# Sheet2.net
KiCad netlist of a schematic drawn in Altium Designer
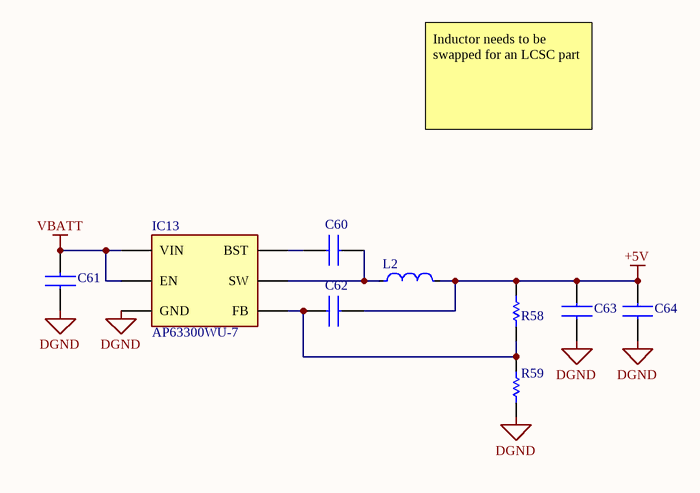
[diagram p0: Sheet2.SchDoc]

(export (version "E")
  (design (tool "Eeschema 10.0.6"))
  (components
    (comp (ref "C60")
      (value "0603,X7R,100nF,50V,10%")
      (footprint "CAPC1608X90N")
      (description "50V 100nF X7R ±10% 0603 Multilayer Ceramic Capacitors MLCC - SMD/SMT ROHS")
      (fields (field (name "LCSC PART #") "C14663") (field (name "MANU PART #") "CC0603KRX7R9BB104"))
      (libsource (lib "flight-controller") (part "CC0603KRX7R9BB104"))
    )
    (comp (ref "C61")
      (value "0805,X7R,10uF,25V,10%")
      (footprint "CAPC2012X145N")
      (description "10uF ±10% 25V Ceramic Capacitor X7R 0805")
      (fields (field (name "LCSC PART #") "C3039694") (field (name "MANU PART #") "CL21B106KAYQNNE"))
      (libsource (lib "flight-controller") (part "CL21B106KAYQNNE"))
    )
    (comp (ref "C62")
      (value "0603,NP0,47pF,50V,5%")
      (footprint "CAPC1608X90N")
      (description "47 pF ±5% 50V Ceramic Capacitor C0G, NP0 0603 (1608 Metric)")
      (fields (field (name "MANU PART #") "CC0603JRNPO9BN470") (field (name "LCSC PART #") "C105622"))
      (libsource (lib "flight-controller") (part "CC0603JRNPO9BN470"))
    )
    (comp (ref "C63")
      (value "0805,X5R,22uF,25V,20%")
      (footprint "CAPC2012X145N")
      (description "22uF ±20% 25V Ceramic Capacitor X5R 0805")
      (fields (field (name "LCSC PART #") "C602037") (field (name "MANU PART #") "CL21A226MAYNNNE"))
      (libsource (lib "flight-controller") (part "CL21A226MAYNNNE"))
    )
    (comp (ref "C64")
      (value "0805,X5R,22uF,25V,20%")
      (footprint "CAPC2012X145N")
      (description "22uF ±20% 25V Ceramic Capacitor X5R 0805")
      (fields (field (name "LCSC PART #") "C602037") (field (name "MANU PART #") "CL21A226MAYNNNE"))
      (libsource (lib "flight-controller") (part "CL21A226MAYNNNE"))
    )
    (comp (ref "IC13")
      (value "AP63300WU-7")
      (footprint "SOT95P280X90-6N")
      (description "Integrated Circuit")
      (fields (field (name "MOUSER PART NUMBER") "621-AP63300WU-7"))
      (libsource (lib "flight-controller") (part "AP63300WU-7"))
    )
    (comp (ref "L2")
      (value "FXL0630-6R8-M")
      (footprint "FXL0630-6R8-M")
      (description "48mΩ 5A 6.8uH 6A Molded Inductor ±20% SMD,7x6.6mm Power Inductors ROHS")
      (fields (field (name "MANUFACTURER") "cjiang (Changjiang Microelectronics Tech)"))
      (libsource (lib "flight-controller") (part "FXL0630-6R8-M"))
    )
    (comp (ref "R58")
      (value "FRC0603F1583TS")
      (footprint "FRC0603F1583TS")
      (fields (field (name "MANUFACTURER") "FOJAN"))
      (libsource (lib "flight-controller") (part "FRC0603F1583TS"))
    )
    (comp (ref "R59")
      (value "RC0603FR-0730K1L")
      (footprint "RC0603FR-0730K1L")
      (fields (field (name "MANUFACTURER") "YAGEO"))
      (libsource (lib "flight-controller") (part "RC0603FR-0730K1L"))
    )
  )
  (nets
    (net (code "1") (name "+5V") (class "Default")
      (node (ref "C62") (pin "1") (pinfunction "1_1") (pintype "passive"))
      (node (ref "C63") (pin "2") (pinfunction "2_2") (pintype "passive"))
      (node (ref "C64") (pin "2") (pinfunction "2_2") (pintype "passive"))
      (node (ref "L2") (pin "2") (pinfunction "2_2") (pintype "passive"))
      (node (ref "R58") (pin "2") (pinfunction "2_2") (pintype "passive"))
    )
    (net (code "2") (name "DGND") (class "Default")
      (node (ref "C61") (pin "2") (pinfunction "2_2") (pintype "passive"))
      (node (ref "C63") (pin "1") (pinfunction "1_1") (pintype "passive"))
      (node (ref "C64") (pin "1") (pinfunction "1_1") (pintype "passive"))
      (node (ref "IC13") (pin "4") (pinfunction "GND_4") (pintype "passive"))
      (node (ref "R59") (pin "1") (pinfunction "1_1") (pintype "passive"))
    )
    (net (code "3") (name "Net-(IC13-BST)") (class "Default")
      (node (ref "C60") (pin "1") (pinfunction "1_1") (pintype "passive"))
      (node (ref "IC13") (pin "6") (pinfunction "BST_6") (pintype "passive"))
    )
    (net (code "4") (name "Net-(IC13-FB)") (class "Default")
      (node (ref "C62") (pin "2") (pinfunction "2_2") (pintype "passive"))
      (node (ref "IC13") (pin "1") (pinfunction "FB_1") (pintype "passive"))
      (node (ref "R58") (pin "1") (pinfunction "1_1") (pintype "passive"))
      (node (ref "R59") (pin "2") (pinfunction "2_2") (pintype "passive"))
    )
    (net (code "5") (name "Net-(IC13-SW)") (class "Default")
      (node (ref "C60") (pin "2") (pinfunction "2_2") (pintype "passive"))
      (node (ref "IC13") (pin "5") (pinfunction "SW_5") (pintype "passive"))
      (node (ref "L2") (pin "1") (pinfunction "1_1") (pintype "passive"))
    )
    (net (code "6") (name "VBATT") (class "Default")
      (node (ref "C61") (pin "1") (pinfunction "1_1") (pintype "passive"))
      (node (ref "IC13") (pin "2") (pinfunction "EN_2") (pintype "passive"))
      (node (ref "IC13") (pin "3") (pinfunction "VIN_3") (pintype "passive"))
    )
  )
)
